# BuckConverter.net
KiCad netlist of a schematic drawn in Altium Designer
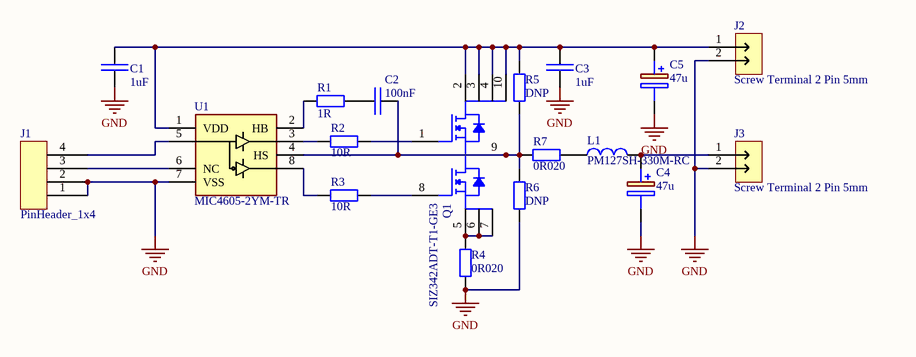
[diagram p0: BuckConverter.SchDoc]

(export (version "E")
  (design (tool "Eeschema 10.0.6"))
  (components
    (comp (ref "C1")
      (value "1uF")
      (footprint "CAP_SM0805_YAGEOCC2_N")
      (description "CAP 1uF SM0805 X7R 25V YAGEO CC2")
      (fields
        (field (name "MANUFACTURER") "Yageo")
        (field (name "MANUFACTURER PART NUMBER") "CC0805KKX7R8BB105")
      )
      (libsource (lib "symbols") (part "CC0805KKX7R8BB105"))
    )
    (comp (ref "C2")
      (value "100nF")
      (footprint "CAP_SM0603_YAGEOCC2_N")
      (description "CAP 100nF SM0603 X7R 50V YAGEO CC2")
      (fields
        (field (name "MANUFACTURER") "Yageo")
        (field (name "MANUFACTURER PART NUMBER") "CC0603KRX7R9BB104")
      )
      (libsource (lib "symbols") (part "CC0603KRX7R9BB104"))
    )
    (comp (ref "C3")
      (value "1uF")
      (footprint "CAP_SM0805_YAGEOCC2_N")
      (description "CAP 1uF SM0805 X7R 25V YAGEO CC2")
      (fields
        (field (name "MANUFACTURER") "Yageo")
        (field (name "MANUFACTURER PART NUMBER") "CC0805KKX7R8BB105")
      )
      (libsource (lib "symbols") (part "CC0805KKX7R8BB105"))
    )
    (comp (ref "C4")
      (value "47u")
      (footprint "CAPAE7366X61N")
      (description "Aluminium Electrolytic Capacitors - SMD 47uF 25V")
      (libsource (lib "symbols") (part "EEE-FK1E470P"))
    )
    (comp (ref "C5")
      (value "47u")
      (footprint "CAPAE7366X61N")
      (description "Aluminium Electrolytic Capacitors - SMD 47uF 25V")
      (libsource (lib "symbols") (part "EEE-FK1E470P"))
    )
    (comp (ref "J1")
      (value "PinHeader_1x4")
      (footprint "PinHeader_1x4_2.54mm")
      (description "PinHeader_1x4 2.54mm Pitch")
      (libsource (lib "symbols") (part "PinHeader_1x4_2.54mm"))
    )
    (comp (ref "J2")
      (value "Screw Terminal 2 Pin 5mm")
      (footprint "TB00250002BE")
      (libsource (lib "symbols") (part "TB00250002BE"))
    )
    (comp (ref "J3")
      (value "Screw Terminal 2 Pin 5mm")
      (footprint "TB00250002BE")
      (libsource (lib "symbols") (part "TB00250002BE"))
    )
    (comp (ref "L1")
      (value "PM127SH-330M-RC")
      (footprint "PM127SH330MRC")
      (fields (field (name "MOUSER PART NUMBER") "542-PM127SH-330M-RC"))
      (libsource (lib "symbols") (part "PM127SH-330M-RC"))
    )
    (comp (ref "Q1")
      (value "SIZ342ADT-T1-GE3")
      (footprint "SIZ342ADT-T1-GE3")
      (description "MOSFET 30V Vds 20V Vgs PowerPAIR 3 x 3")
      (fields (field (name "MOUSER PART NUMBER") "78-SIZ342ADT-T1-GE3"))
      (libsource (lib "symbols") (part "SIZ342ADT-T1-GE3"))
    )
    (comp (ref "R1")
      (value "1R")
      (footprint "RES_SM0603_YAGEORC_N")
      (description "RES 1R SM0603YAGEO RC_L")
      (fields
        (field (name "MANUFACTURER") "Yageo")
        (field (name "MANUFACTURER PART NUMBER") "RC0805FR-0710RL")
      )
      (libsource (lib "symbols") (part "RC0603FR-071RL"))
    )
    (comp (ref "R2")
      (value "10R")
      (footprint "RES_SM0603_YAGEORC_N")
      (description "RES 10R SM0603 YAGEO RC_L")
      (fields
        (field (name "MANUFACTURER") "Yageo")
        (field (name "MANUFACTURER PART NUMBER") "RC0603FR-0710RL")
      )
      (libsource (lib "symbols") (part "RC0603FR-0710RL"))
    )
    (comp (ref "R3")
      (value "10R")
      (footprint "RES_SM0603_YAGEORC_N")
      (description "RES 10R SM0603 YAGEO RC_L")
      (fields
        (field (name "MANUFACTURER") "Yageo")
        (field (name "MANUFACTURER PART NUMBER") "RC0603FR-0710RL")
      )
      (libsource (lib "symbols") (part "RC0603FR-0710RL"))
    )
    (comp (ref "R4")
      (value "0R020")
      (footprint "MSMA2512R0200FGN")
      (description "RES SM0603YAGEO RC_L")
      (libsource (lib "symbols") (part "MSMA2512R0200FGN"))
    )
    (comp (ref "R5")
      (value "DNP")
      (footprint "RES_SM0603_YAGEORC_N")
      (description "RES SM0603YAGEO RC_L")
      (fields
        (field (name "MANUFACTURER") "Yageo")
        (field (name "MANUFACTURER PART NUMBER") "RC0805FR-0710RL")
      )
      (libsource (lib "symbols") (part "Resistor"))
    )
    (comp (ref "R6")
      (value "DNP")
      (footprint "RES_SM0603_YAGEORC_N")
      (description "RES SM0603YAGEO RC_L")
      (fields
        (field (name "MANUFACTURER") "Yageo")
        (field (name "MANUFACTURER PART NUMBER") "RC0805FR-0710RL")
      )
      (libsource (lib "symbols") (part "Resistor"))
    )
    (comp (ref "R7")
      (value "0R020")
      (footprint "MSMA2512R0200FGN")
      (description "RES SM0603YAGEO RC_L")
      (libsource (lib "") (part "MSMA2512R0200FGN_1"))
    )
    (comp (ref "U1")
      (value "MIC4605-2YM-TR")
      (footprint "SOIC127P600X163-8N")
      (description "Gate Drivers 85V Half Bridge MOSFET Driver")
      (fields (field (name "MOUSER PART NUMBER") "998-MIC4605-2YM-TR"))
      (libsource (lib "symbols") (part "MIC4605-2YM-TR"))
    )
  )
  (nets
    (net (code "1") (name "GND") (class "Default")
      (node (ref "C1") (pin "2") (pintype "passive"))
      (node (ref "C3") (pin "2") (pintype "passive"))
      (node (ref "C4") (pin "2") (pinfunction "-_2") (pintype "passive"))
      (node (ref "C5") (pin "2") (pinfunction "-_2") (pintype "passive"))
      (node (ref "J1") (pin "1") (pintype "passive"))
      (node (ref "J1") (pin "2") (pintype "passive"))
      (node (ref "J2") (pin "2") (pinfunction "2_2") (pintype "passive"))
      (node (ref "J3") (pin "2") (pinfunction "2_2") (pintype "passive"))
      (node (ref "R4") (pin "1") (pintype "passive"))
      (node (ref "R6") (pin "1") (pintype "passive"))
      (node (ref "U1") (pin "7") (pinfunction "VSS_7") (pintype "passive"))
    )
    (net (code "2") (name "Net-(C2-Pad1)") (class "Default")
      (node (ref "C2") (pin "1") (pintype "passive"))
      (node (ref "R1") (pin "2") (pintype "passive"))
    )
    (net (code "3") (name "Net-(C4-+)") (class "Default")
      (node (ref "C4") (pin "1") (pinfunction "+_1") (pintype "passive"))
      (node (ref "J3") (pin "1") (pinfunction "1_1") (pintype "passive"))
      (node (ref "L1") (pin "2") (pinfunction "2_2") (pintype "passive"))
    )
    (net (code "4") (name "Net-(C5-+)") (class "Default")
      (node (ref "C1") (pin "1") (pintype "passive"))
      (node (ref "C3") (pin "1") (pintype "passive"))
      (node (ref "C5") (pin "1") (pinfunction "+_1") (pintype "passive"))
      (node (ref "J2") (pin "1") (pinfunction "1_1") (pintype "passive"))
      (node (ref "Q1") (pin "10") (pinfunction "D_10") (pintype "passive"))
      (node (ref "Q1") (pin "2") (pinfunction "D_2") (pintype "passive"))
      (node (ref "Q1") (pin "3") (pinfunction "D_3") (pintype "passive"))
      (node (ref "Q1") (pin "4") (pinfunction "D_4") (pintype "passive"))
      (node (ref "R5") (pin "2") (pintype "passive"))
      (node (ref "U1") (pin "1") (pinfunction "VDD_1") (pintype "passive"))
    )
    (net (code "5") (name "Net-(L1-Pad1)") (class "Default")
      (node (ref "L1") (pin "1") (pinfunction "1_1") (pintype "passive"))
      (node (ref "R7") (pin "1") (pintype "passive"))
    )
    (net (code "6") (name "Net-(Q1-D-Pad5)") (class "Default")
      (node (ref "Q1") (pin "5") (pinfunction "D_5") (pintype "passive"))
      (node (ref "Q1") (pin "6") (pinfunction "D_6") (pintype "passive"))
      (node (ref "Q1") (pin "7") (pinfunction "D_7") (pintype "passive"))
      (node (ref "R4") (pin "2") (pintype "passive"))
    )
    (net (code "7") (name "Net-(Q1-G1)") (class "Default")
      (node (ref "Q1") (pin "1") (pinfunction "G1_1") (pintype "passive"))
      (node (ref "R2") (pin "2") (pintype "passive"))
    )
    (net (code "8") (name "Net-(Q1-G2)") (class "Default")
      (node (ref "Q1") (pin "8") (pinfunction "G2_8") (pintype "passive"))
      (node (ref "R3") (pin "2") (pintype "passive"))
    )
    (net (code "9") (name "Net-(U1-HB)") (class "Default")
      (node (ref "R1") (pin "1") (pintype "passive"))
      (node (ref "U1") (pin "2") (pinfunction "HB_2") (pintype "passive"))
    )
    (net (code "10") (name "Net-(U1-HO)") (class "Default")
      (node (ref "R2") (pin "1") (pintype "passive"))
      (node (ref "U1") (pin "3") (pinfunction "HO_3") (pintype "passive"))
    )
    (net (code "11") (name "Net-(U1-HS)") (class "Default")
      (node (ref "C2") (pin "2") (pintype "passive"))
      (node (ref "Q1") (pin "9") (pinfunction "D_9") (pintype "passive"))
      (node (ref "R5") (pin "1") (pintype "passive"))
      (node (ref "R6") (pin "2") (pintype "passive"))
      (node (ref "R7") (pin "2") (pintype "passive"))
      (node (ref "U1") (pin "4") (pinfunction "HS_4") (pintype "passive"))
    )
    (net (code "12") (name "Net-(U1-LO)") (class "Default")
      (node (ref "R3") (pin "1") (pintype "passive"))
      (node (ref "U1") (pin "8") (pinfunction "LO_8") (pintype "passive"))
    )
    (net (code "13") (name "Net-(U1-NC)") (class "Default")
      (node (ref "J1") (pin "3") (pintype "passive"))
      (node (ref "U1") (pin "6") (pinfunction "NC_6") (pintype "passive"))
    )
    (net (code "14") (name "Net-(U1-PWM)") (class "Default")
      (node (ref "J1") (pin "4") (pintype "passive"))
      (node (ref "U1") (pin "5") (pinfunction "PWM_5") (pintype "passive"))
    )
  )
)
